# DAU_Kupplung_3phasig_V1_8.net
KiCad netlist of a schematic drawn in EAGLE
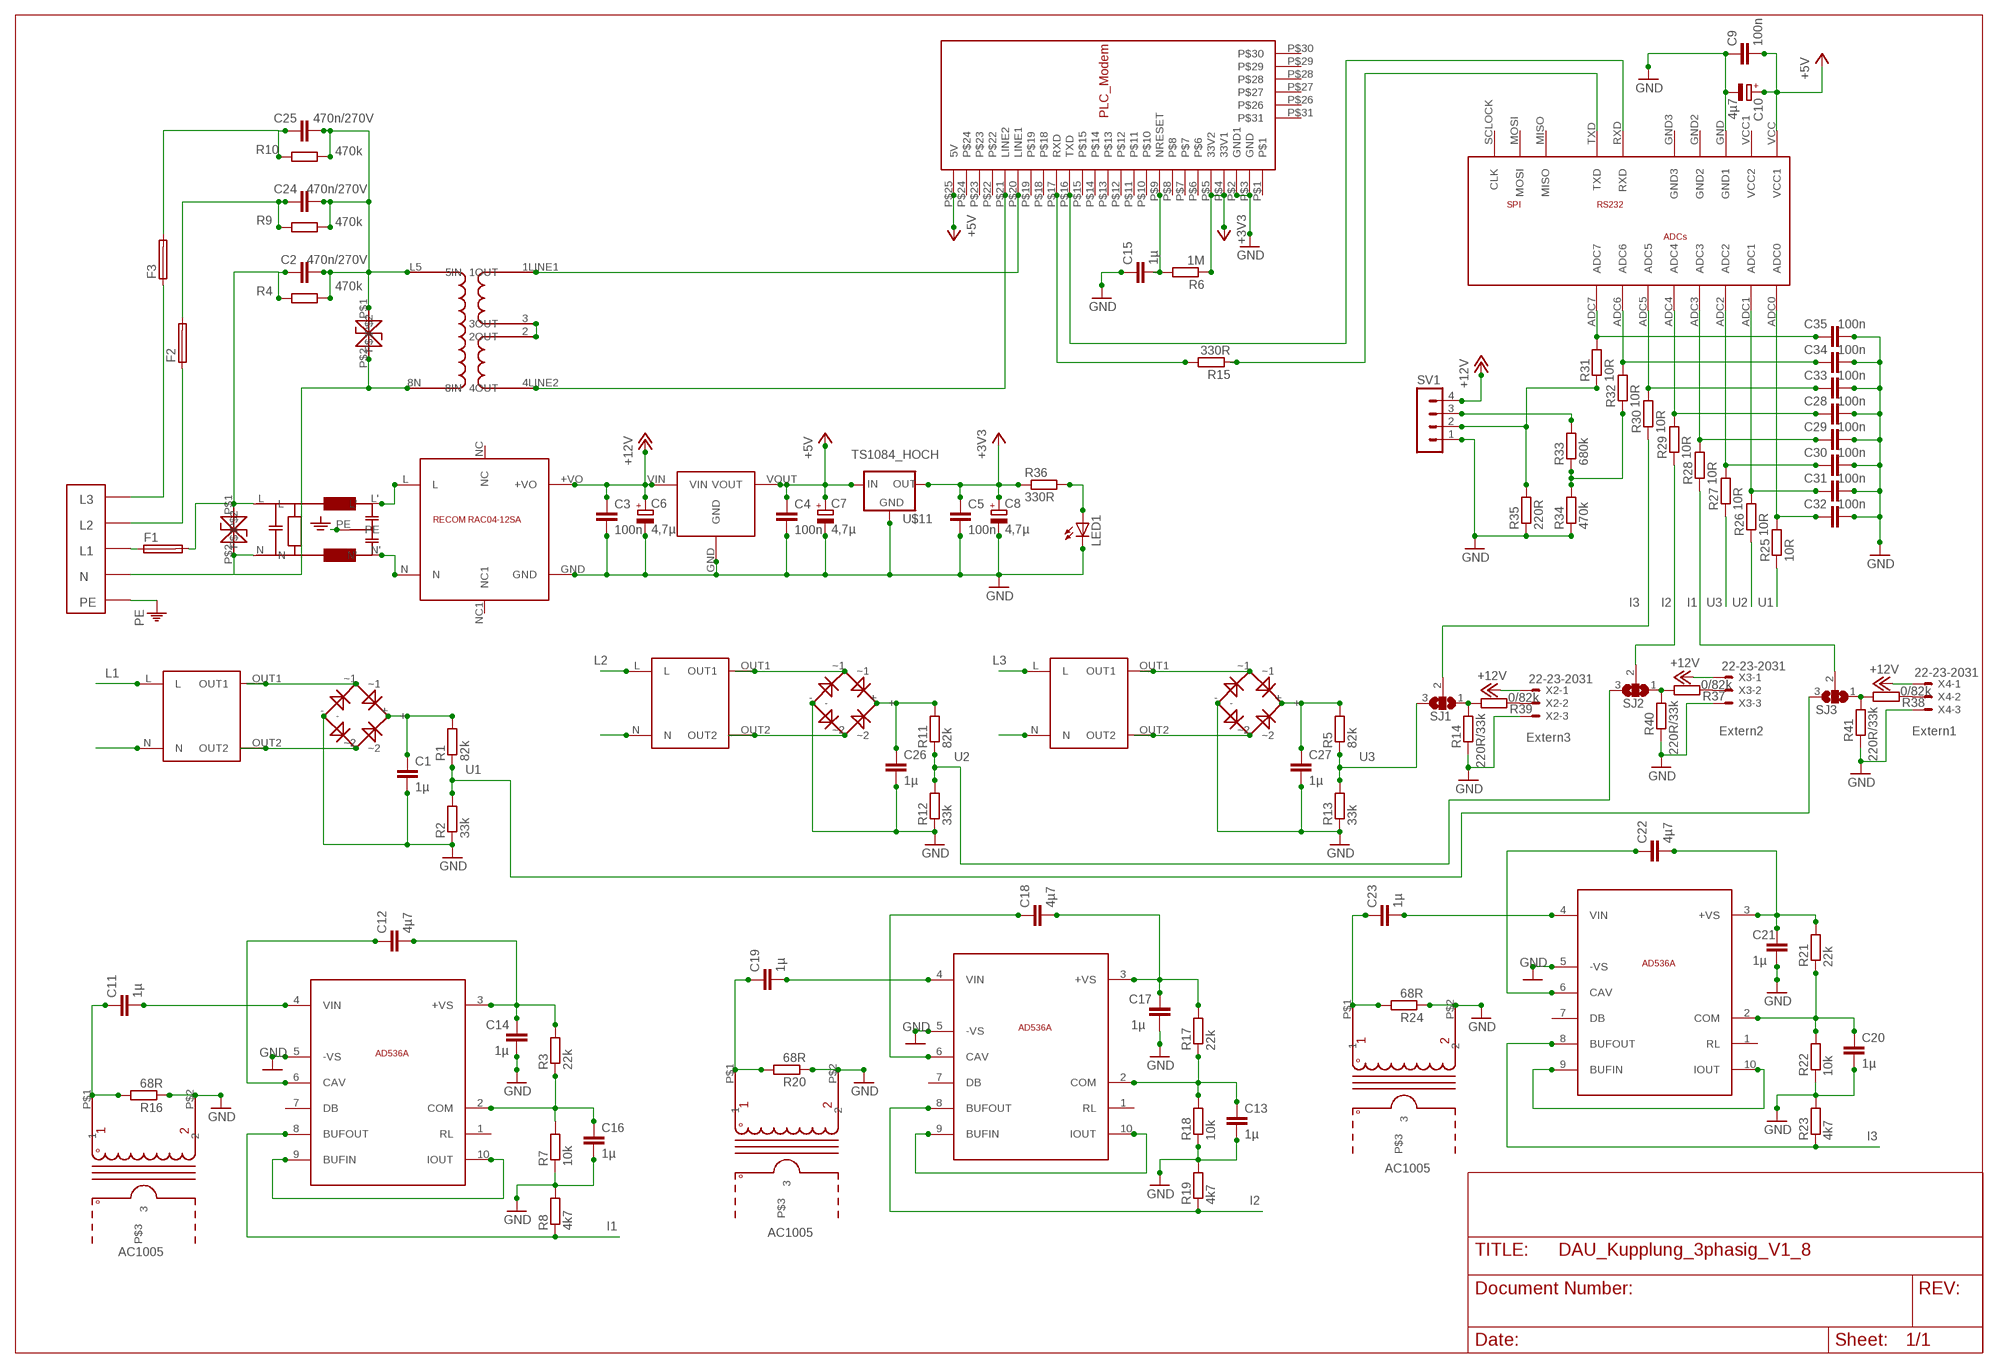
[diagram p0: schematic, sheet 1]

(export (version "E")
  (design (tool "Eeschema 10.0.6"))
  (components
    (comp (ref "AC1002_1")
      (value "AC1010")
      (footprint "eagle-import:AC1010")
      (libsource (lib "eagle-import") (part "AC1010"))
    )
    (comp (ref "C1")
      (value "1µ")
      (footprint "eagle-import:C0805K")
      (libsource (lib "eagle-import") (part "C-EUC0805K"))
    )
    (comp (ref "C2")
      (value "470n/270V")
      (footprint "eagle-import:C225-087X268")
      (libsource (lib "eagle-import") (part "C-EU225-087X268"))
    )
    (comp (ref "C3")
      (value "100n")
      (footprint "eagle-import:C0805K")
      (libsource (lib "eagle-import") (part "C-EUC0805K"))
    )
    (comp (ref "C4")
      (value "100n")
      (footprint "eagle-import:C0805K")
      (libsource (lib "eagle-import") (part "C-EUC0805K"))
    )
    (comp (ref "C5")
      (value "100n")
      (footprint "eagle-import:C0805K")
      (libsource (lib "eagle-import") (part "C-EUC0805K"))
    )
    (comp (ref "C6")
      (value "4,7µ")
      (footprint "eagle-import:E2,5-6")
      (libsource (lib "eagle-import") (part "resistor_CPOL-EUE2.5-6"))
    )
    (comp (ref "C7")
      (value "4,7µ")
      (footprint "eagle-import:E2,5-6")
      (libsource (lib "eagle-import") (part "resistor_CPOL-EUE2.5-6"))
    )
    (comp (ref "C8")
      (value "4,7µ")
      (footprint "eagle-import:E2,5-6")
      (libsource (lib "eagle-import") (part "resistor_CPOL-EUE2.5-6"))
    )
    (comp (ref "C9")
      (value "100n")
      (footprint "eagle-import:C0805K")
      (libsource (lib "eagle-import") (part "C-EUC0805K"))
    )
    (comp (ref "C10")
      (value "4µ7")
      (footprint "eagle-import:E2,5-6E")
      (libsource (lib "eagle-import") (part "CPOL-EUE2,5-6E"))
    )
    (comp (ref "C11")
      (value "1µ")
      (footprint "eagle-import:C0805K")
      (libsource (lib "eagle-import") (part "C-EUC0805K"))
    )
    (comp (ref "C12")
      (value "4µ7")
      (footprint "eagle-import:C0805K")
      (libsource (lib "eagle-import") (part "C-EUC0805K"))
    )
    (comp (ref "C13")
      (value "1µ")
      (footprint "eagle-import:C0805K")
      (libsource (lib "eagle-import") (part "C-EUC0805K"))
    )
    (comp (ref "C14")
      (value "1µ")
      (footprint "eagle-import:C0805K")
      (libsource (lib "eagle-import") (part "C-EUC0805K"))
    )
    (comp (ref "C15")
      (value "1µ")
      (footprint "eagle-import:C0805K")
      (libsource (lib "eagle-import") (part "C-EUC0805K"))
    )
    (comp (ref "C16")
      (value "1µ")
      (footprint "eagle-import:C0805K")
      (libsource (lib "eagle-import") (part "C-EUC0805K"))
    )
    (comp (ref "C17")
      (value "1µ")
      (footprint "eagle-import:C0805K")
      (libsource (lib "eagle-import") (part "C-EUC0805K"))
    )
    (comp (ref "C18")
      (value "4µ7")
      (footprint "eagle-import:C0805K")
      (libsource (lib "eagle-import") (part "C-EUC0805K"))
    )
    (comp (ref "C19")
      (value "1µ")
      (footprint "eagle-import:C0805K")
      (libsource (lib "eagle-import") (part "C-EUC0805K"))
    )
    (comp (ref "C20")
      (value "1µ")
      (footprint "eagle-import:C0805K")
      (libsource (lib "eagle-import") (part "C-EUC0805K"))
    )
    (comp (ref "C21")
      (value "1µ")
      (footprint "eagle-import:C0805K")
      (libsource (lib "eagle-import") (part "C-EUC0805K"))
    )
    (comp (ref "C22")
      (value "4µ7")
      (footprint "eagle-import:C0805K")
      (libsource (lib "eagle-import") (part "C-EUC0805K"))
    )
    (comp (ref "C23")
      (value "1µ")
      (footprint "eagle-import:C0805K")
      (libsource (lib "eagle-import") (part "C-EUC0805K"))
    )
    (comp (ref "C24")
      (value "470n/270V")
      (footprint "eagle-import:C225-087X268")
      (libsource (lib "eagle-import") (part "C-EU225-087X268"))
    )
    (comp (ref "C25")
      (value "470n/270V")
      (footprint "eagle-import:C225-087X268")
      (libsource (lib "eagle-import") (part "C-EU225-087X268"))
    )
    (comp (ref "C26")
      (value "1µ")
      (footprint "eagle-import:C0805K")
      (libsource (lib "eagle-import") (part "C-EUC0805K"))
    )
    (comp (ref "C27")
      (value "1µ")
      (footprint "eagle-import:C0805K")
      (libsource (lib "eagle-import") (part "C-EUC0805K"))
    )
    (comp (ref "C28")
      (value "100n")
      (footprint "eagle-import:C0805K")
      (libsource (lib "eagle-import") (part "C-EUC0805K"))
    )
    (comp (ref "C29")
      (value "100n")
      (footprint "eagle-import:C0805K")
      (libsource (lib "eagle-import") (part "C-EUC0805K"))
    )
    (comp (ref "C30")
      (value "100n")
      (footprint "eagle-import:C0805K")
      (libsource (lib "eagle-import") (part "C-EUC0805K"))
    )
    (comp (ref "C31")
      (value "100n")
      (footprint "eagle-import:C0805K")
      (libsource (lib "eagle-import") (part "C-EUC0805K"))
    )
    (comp (ref "C32")
      (value "100n")
      (footprint "eagle-import:C0805K")
      (libsource (lib "eagle-import") (part "C-EUC0805K"))
    )
    (comp (ref "C33")
      (value "100n")
      (footprint "eagle-import:C0805K")
      (libsource (lib "eagle-import") (part "C-EUC0805K"))
    )
    (comp (ref "C34")
      (value "100n")
      (footprint "eagle-import:C0805K")
      (libsource (lib "eagle-import") (part "C-EUC0805K"))
    )
    (comp (ref "C35")
      (value "100n")
      (footprint "eagle-import:C0805K")
      (libsource (lib "eagle-import") (part "C-EUC0805K"))
    )
    (comp (ref "F1")
      (value "TR5")
      (footprint "eagle-import:TR5")
      (libsource (lib "eagle-import") (part "TR5"))
    )
    (comp (ref "F2")
      (value "TR5")
      (footprint "eagle-import:TR5")
      (fields (field (name "OC_FARNELL") "unknown") (field (name "OC_NEWARK") "unknown"))
      (libsource (lib "eagle-import") (part "TR5"))
    )
    (comp (ref "F3")
      (value "TR5")
      (footprint "eagle-import:TR5")
      (fields (field (name "OC_FARNELL") "unknown") (field (name "OC_NEWARK") "unknown"))
      (libsource (lib "eagle-import") (part "TR5"))
    )
    (comp (ref "LED1")
      (value "LEDSQR2X5")
      (footprint "eagle-import:LED2X5")
      (libsource (lib "eagle-import") (part "LEDSQR2X5"))
    )
    (comp (ref "P6KE300CA")
      (value "P6KE300CA")
      (footprint "eagle-import:TSV")
      (libsource (lib "eagle-import") (part "TSV"))
    )
    (comp (ref "R1")
      (value "82k")
      (footprint "eagle-import:R0805")
      (libsource (lib "eagle-import") (part "R-EU_R0805"))
    )
    (comp (ref "R2")
      (value "33k")
      (footprint "eagle-import:R0805")
      (libsource (lib "eagle-import") (part "R-EU_R0805"))
    )
    (comp (ref "R3")
      (value "22k")
      (footprint "eagle-import:R0805")
      (libsource (lib "eagle-import") (part "R-EU_R0805"))
    )
    (comp (ref "R4")
      (value "470k")
      (footprint "eagle-import:0204_7")
      (libsource (lib "eagle-import") (part "R-EU_0204/7"))
    )
    (comp (ref "R5")
      (value "82k")
      (footprint "eagle-import:R0805")
      (libsource (lib "eagle-import") (part "R-EU_R0805"))
    )
    (comp (ref "R6")
      (value "1M")
      (footprint "eagle-import:R0805")
      (libsource (lib "eagle-import") (part "R-EU_R0805"))
    )
    (comp (ref "R7")
      (value "10k")
      (footprint "eagle-import:R0805")
      (libsource (lib "eagle-import") (part "R-EU_R0805"))
    )
    (comp (ref "R8")
      (value "4k7")
      (footprint "eagle-import:R0805")
      (libsource (lib "eagle-import") (part "R-EU_R0805"))
    )
    (comp (ref "R9")
      (value "470k")
      (footprint "eagle-import:0204_7")
      (libsource (lib "eagle-import") (part "R-EU_0204/7"))
    )
    (comp (ref "R10")
      (value "470k")
      (footprint "eagle-import:0204_7")
      (libsource (lib "eagle-import") (part "R-EU_0204/7"))
    )
    (comp (ref "R11")
      (value "82k")
      (footprint "eagle-import:R0805")
      (libsource (lib "eagle-import") (part "R-EU_R0805"))
    )
    (comp (ref "R12")
      (value "33k")
      (footprint "eagle-import:R0805")
      (libsource (lib "eagle-import") (part "R-EU_R0805"))
    )
    (comp (ref "R13")
      (value "33k")
      (footprint "eagle-import:R0805")
      (libsource (lib "eagle-import") (part "R-EU_R0805"))
    )
    (comp (ref "R14")
      (value "220R/33k")
      (footprint "eagle-import:R0805")
      (libsource (lib "eagle-import") (part "R-EU_R0805"))
    )
    (comp (ref "R15")
      (value "330R")
      (footprint "eagle-import:R0805")
      (libsource (lib "eagle-import") (part "R-EU_R0805"))
    )
    (comp (ref "R16")
      (value "68R")
      (footprint "eagle-import:0204_7")
      (libsource (lib "eagle-import") (part "R-EU_0204/7"))
    )
    (comp (ref "R17")
      (value "22k")
      (footprint "eagle-import:R0805")
      (libsource (lib "eagle-import") (part "R-EU_R0805"))
    )
    (comp (ref "R18")
      (value "10k")
      (footprint "eagle-import:R0805")
      (libsource (lib "eagle-import") (part "R-EU_R0805"))
    )
    (comp (ref "R19")
      (value "4k7")
      (footprint "eagle-import:R0805")
      (libsource (lib "eagle-import") (part "R-EU_R0805"))
    )
    (comp (ref "R20")
      (value "68R")
      (footprint "eagle-import:0204_7")
      (libsource (lib "eagle-import") (part "R-EU_0204/7"))
    )
    (comp (ref "R21")
      (value "22k")
      (footprint "eagle-import:R0805")
      (libsource (lib "eagle-import") (part "R-EU_R0805"))
    )
    (comp (ref "R22")
      (value "10k")
      (footprint "eagle-import:R0805")
      (libsource (lib "eagle-import") (part "R-EU_R0805"))
    )
    (comp (ref "R23")
      (value "4k7")
      (footprint "eagle-import:R0805")
      (libsource (lib "eagle-import") (part "R-EU_R0805"))
    )
    (comp (ref "R24")
      (value "68R")
      (footprint "eagle-import:0204_7")
      (libsource (lib "eagle-import") (part "R-EU_0204/7"))
    )
    (comp (ref "R25")
      (value "10R")
      (footprint "eagle-import:R0805")
      (libsource (lib "eagle-import") (part "R-EU_R0805"))
    )
    (comp (ref "R26")
      (value "10R")
      (footprint "eagle-import:R0805")
      (libsource (lib "eagle-import") (part "R-EU_R0805"))
    )
    (comp (ref "R27")
      (value "10R")
      (footprint "eagle-import:R0805")
      (libsource (lib "eagle-import") (part "R-EU_R0805"))
    )
    (comp (ref "R28")
      (value "10R")
      (footprint "eagle-import:R0805")
      (libsource (lib "eagle-import") (part "R-EU_R0805"))
    )
    (comp (ref "R29")
      (value "10R")
      (footprint "eagle-import:R0805")
      (libsource (lib "eagle-import") (part "R-EU_R0805"))
    )
    (comp (ref "R30")
      (value "10R")
      (footprint "eagle-import:R0805")
      (libsource (lib "eagle-import") (part "R-EU_R0805"))
    )
    (comp (ref "R31")
      (value "10R")
      (footprint "eagle-import:R0805")
      (libsource (lib "eagle-import") (part "R-EU_R0805"))
    )
    (comp (ref "R32")
      (value "10R")
      (footprint "eagle-import:R0805")
      (libsource (lib "eagle-import") (part "R-EU_R0805"))
    )
    (comp (ref "R33")
      (value "680k")
      (footprint "eagle-import:R0805")
      (libsource (lib "eagle-import") (part "R-EU_R0805"))
    )
    (comp (ref "R34")
      (value "470k")
      (footprint "eagle-import:R0805")
      (libsource (lib "eagle-import") (part "R-EU_R0805"))
    )
    (comp (ref "R35")
      (value "220R")
      (footprint "eagle-import:R0805")
      (libsource (lib "eagle-import") (part "R-EU_R0805"))
    )
    (comp (ref "R36")
      (value "330R")
      (footprint "eagle-import:R0805")
      (libsource (lib "eagle-import") (part "R-EU_R0805"))
    )
    (comp (ref "R37")
      (value "0/82k")
      (footprint "eagle-import:R0805")
      (libsource (lib "eagle-import") (part "R-EU_R0805"))
    )
    (comp (ref "R38")
      (value "0/82k")
      (footprint "eagle-import:R0805")
      (libsource (lib "eagle-import") (part "R-EU_R0805"))
    )
    (comp (ref "R39")
      (value "0/82k")
      (footprint "eagle-import:R0805")
      (libsource (lib "eagle-import") (part "R-EU_R0805"))
    )
    (comp (ref "R40")
      (value "220R/33k")
      (footprint "eagle-import:R0805")
      (libsource (lib "eagle-import") (part "R-EU_R0805"))
    )
    (comp (ref "R41")
      (value "220R/33k")
      (footprint "eagle-import:R0805")
      (libsource (lib "eagle-import") (part "R-EU_R0805"))
    )
    (comp (ref "SJ1")
      (value "SJ2WW")
      (footprint "eagle-import:SJ_2W")
      (libsource (lib "eagle-import") (part "SJ2WW"))
    )
    (comp (ref "SJ2")
      (value "SJ2WW")
      (footprint "eagle-import:SJ_2W")
      (libsource (lib "eagle-import") (part "SJ2WW"))
    )
    (comp (ref "SJ3")
      (value "SJ2WW")
      (footprint "eagle-import:SJ_2W")
      (libsource (lib "eagle-import") (part "SJ2WW"))
    )
    (comp (ref "SV1")
      (value "MA04-1")
      (footprint "eagle-import:MA04-1")
      (libsource (lib "eagle-import") (part "MA04-1"))
    )
    (comp (ref "TSV2")
      (value "TSV")
      (footprint "eagle-import:TSV")
      (libsource (lib "eagle-import") (part "TSV"))
    )
    (comp (ref "U$1")
      (value "RECOM_RAC04_12SA")
      (footprint "eagle-import:RAC04_12SA")
      (libsource (lib "eagle-import") (part "RECOM_RAC04_12SA"))
    )
    (comp (ref "U$2")
      (value "SICHERHEITSTRAFO")
      (footprint "eagle-import:TRAFO_0,35VA")
      (libsource (lib "eagle-import") (part "SICHERHEITSTRAFO"))
    )
    (comp (ref "U$3")
      (value "ADUC831_MINIMUM")
      (footprint "eagle-import:ADUC_MINIMUM")
      (libsource (lib "eagle-import") (part "ADUC831_MINIMUM"))
    )
    (comp (ref "U$4")
      (value "MODEMSTECKER")
      (footprint "eagle-import:MODEM_FUSS")
      (libsource (lib "eagle-import") (part "MODEMSTECKER"))
    )
    (comp (ref "U$5")
      (value "PLC_UEBERTRAGER_V2")
      (footprint "eagle-import:PLC-UEBERTRAGER_V2")
      (libsource (lib "eagle-import") (part "PLC_UEBERTRAGER_V2"))
    )
    (comp (ref "U$7")
      (value "AC1010")
      (footprint "eagle-import:AC1010")
      (libsource (lib "eagle-import") (part "AC1010"))
    )
    (comp (ref "U$8")
      (value "RECTIFIER")
      (footprint "eagle-import:RECTIFIER")
      (libsource (lib "eagle-import") (part "RECTIFIER"))
    )
    (comp (ref "U$10")
      (value "RECOM_785_05")
      (footprint "eagle-import:RECOM785X")
      (libsource (lib "eagle-import") (part "RECOM_785_05"))
    )
    (comp (ref "U$11")
      (value "TS1084_HOCH")
      (footprint "eagle-import:TS1084_HOCH")
      (libsource (lib "eagle-import") (part "TS1084_HOCH"))
    )
    (comp (ref "U$12")
      (value "AD536")
      (footprint "eagle-import:TO100_10PIN")
      (libsource (lib "eagle-import") (part "AD536"))
    )
    (comp (ref "U$13")
      (value "AD536")
      (footprint "eagle-import:TO100_10PIN")
      (libsource (lib "eagle-import") (part "AD536"))
    )
    (comp (ref "U$14")
      (value "AC1010")
      (footprint "eagle-import:AC1010")
      (libsource (lib "eagle-import") (part "AC1010"))
    )
    (comp (ref "U$15")
      (value "AD536")
      (footprint "eagle-import:TO100_10PIN")
      (libsource (lib "eagle-import") (part "AD536"))
    )
    (comp (ref "U$16")
      (value "SICHERHEITSTRAFO")
      (footprint "eagle-import:TRAFO_0,35VA")
      (libsource (lib "eagle-import") (part "SICHERHEITSTRAFO"))
    )
    (comp (ref "U$17")
      (value "RECTIFIER")
      (footprint "eagle-import:RECTIFIER")
      (libsource (lib "eagle-import") (part "RECTIFIER"))
    )
    (comp (ref "U$18")
      (value "SICHERHEITSTRAFO")
      (footprint "eagle-import:TRAFO_0,35VA")
      (libsource (lib "eagle-import") (part "SICHERHEITSTRAFO"))
    )
    (comp (ref "U$19")
      (value "RECTIFIER")
      (footprint "eagle-import:RECTIFIER")
      (libsource (lib "eagle-import") (part "RECTIFIER"))
    )
    (comp (ref "U$20")
      (value "NETZFILTER_05_A")
      (footprint "eagle-import:NETZFILTER")
      (libsource (lib "eagle-import") (part "NETZFILTER_05_A"))
    )
    (comp (ref "X1")
      (value "CONNECTO_5_POL")
      (footprint "eagle-import:CONNECTOR_5_POL")
      (libsource (lib "eagle-import") (part "CONNECTO_5_POL"))
    )
    (comp (ref "X2")
      (value "22-23-2031")
      (footprint "eagle-import:22-23-2031")
      (fields (field (name "MF") "MOLEX"))
      (libsource (lib "eagle-import") (part "22-23-2031"))
    )
    (comp (ref "X3")
      (value "22-23-2031")
      (footprint "eagle-import:22-23-2031")
      (fields (field (name "MF") "MOLEX"))
      (libsource (lib "eagle-import") (part "22-23-2031"))
    )
    (comp (ref "X4")
      (value "22-23-2031")
      (footprint "eagle-import:22-23-2031")
      (fields (field (name "MF") "MOLEX"))
      (libsource (lib "eagle-import") (part "22-23-2031"))
    )
  )
  (nets
    (net (code "1") (name "+3V3") (class "Default")
      (node (ref "C5") (pin "1") (pinfunction "1_1") (pintype "passive"))
      (node (ref "C8") (pin "+") (pinfunction "+_+") (pintype "passive"))
      (node (ref "R36") (pin "1") (pinfunction "1_1") (pintype "passive"))
      (node (ref "R6") (pin "1") (pinfunction "1_1") (pintype "passive"))
      (node (ref "U$11") (pin "OUT") (pinfunction "OUT_OUT") (pintype "passive"))
      (node (ref "U$4") (pin "P$4") (pinfunction "33V1_P$4") (pintype "bidirectional"))
      (node (ref "U$4") (pin "P$5") (pinfunction "33V2_P$5") (pintype "bidirectional"))
    )
    (net (code "2") (name "+5V") (class "Default")
      (node (ref "C10") (pin "+") (pinfunction "+_+") (pintype "passive"))
      (node (ref "C4") (pin "1") (pinfunction "1_1") (pintype "passive"))
      (node (ref "C7") (pin "+") (pinfunction "+_+") (pintype "passive"))
      (node (ref "C9") (pin "2") (pinfunction "2_2") (pintype "passive"))
      (node (ref "U$10") (pin "VOUT") (pinfunction "VOUT_VOUT") (pintype "bidirectional"))
      (node (ref "U$11") (pin "IN") (pinfunction "IN_IN") (pintype "input"))
      (node (ref "U$3") (pin "VCC") (pinfunction "VCC1_VCC") (pintype "bidirectional"))
      (node (ref "U$4") (pin "P$25") (pinfunction "5V_P$25") (pintype "bidirectional"))
    )
    (net (code "3") (name "+12V") (class "Default")
      (node (ref "C3") (pin "1") (pinfunction "1_1") (pintype "passive"))
      (node (ref "C6") (pin "+") (pinfunction "+_+") (pintype "passive"))
      (node (ref "SV1") (pin "4") (pinfunction "4_4") (pintype "passive"))
      (node (ref "U$1") (pin "+VO") (pinfunction "+VO_+VO") (pintype "bidirectional"))
      (node (ref "U$10") (pin "VIN") (pinfunction "VIN_VIN") (pintype "bidirectional"))
      (node (ref "X2") (pin "1") (pinfunction "S_1") (pintype "passive"))
      (node (ref "X3") (pin "1") (pinfunction "S_1") (pintype "passive"))
      (node (ref "X4") (pin "1") (pinfunction "S_1") (pintype "passive"))
    )
    (net (code "4") (name "/I1") (class "Default")
      (node (ref "R28") (pin "1") (pinfunction "1_1") (pintype "passive"))
      (node (ref "R8") (pin "1") (pinfunction "1_1") (pintype "passive"))
      (node (ref "SJ3") (pin "2") (pinfunction "2_2") (pintype "passive"))
      (node (ref "U$13") (pin "8") (pinfunction "BUFOUT_8") (pintype "bidirectional"))
    )
    (net (code "5") (name "/I2") (class "Default")
      (node (ref "R19") (pin "1") (pinfunction "1_1") (pintype "passive"))
      (node (ref "R29") (pin "1") (pinfunction "1_1") (pintype "passive"))
      (node (ref "SJ2") (pin "2") (pinfunction "2_2") (pintype "passive"))
      (node (ref "U$12") (pin "8") (pinfunction "BUFOUT_8") (pintype "bidirectional"))
    )
    (net (code "6") (name "/I3") (class "Default")
      (node (ref "R23") (pin "1") (pinfunction "1_1") (pintype "passive"))
      (node (ref "R30") (pin "1") (pinfunction "1_1") (pintype "passive"))
      (node (ref "SJ1") (pin "2") (pinfunction "2_2") (pintype "passive"))
      (node (ref "U$15") (pin "8") (pinfunction "BUFOUT_8") (pintype "bidirectional"))
    )
    (net (code "7") (name "/L1") (class "Default")
      (node (ref "C2") (pin "1") (pinfunction "1_1") (pintype "passive"))
      (node (ref "F1") (pin "2") (pinfunction "2_2") (pintype "passive"))
      (node (ref "P6KE300CA") (pin "P$1") (pinfunction "P$1_P$1") (pintype "bidirectional"))
      (node (ref "R4") (pin "2") (pinfunction "2_2") (pintype "passive"))
      (node (ref "U$2") (pin "L") (pinfunction "L_L") (pintype "bidirectional"))
      (node (ref "U$20") (pin "L") (pinfunction "L_L") (pintype "bidirectional"))
    )
    (net (code "8") (name "/L2") (class "Default")
      (node (ref "C24") (pin "1") (pinfunction "1_1") (pintype "passive"))
      (node (ref "F2") (pin "2") (pinfunction "2_2") (pintype "passive"))
      (node (ref "R9") (pin "2") (pinfunction "2_2") (pintype "passive"))
      (node (ref "U$16") (pin "L") (pinfunction "L_L") (pintype "bidirectional"))
    )
    (net (code "9") (name "/L3") (class "Default")
      (node (ref "C25") (pin "1") (pinfunction "1_1") (pintype "passive"))
      (node (ref "F3") (pin "2") (pinfunction "2_2") (pintype "passive"))
      (node (ref "R10") (pin "2") (pinfunction "2_2") (pintype "passive"))
      (node (ref "U$18") (pin "L") (pinfunction "L_L") (pintype "bidirectional"))
    )
    (net (code "10") (name "/N") (class "Default")
      (node (ref "P6KE300CA") (pin "P$2") (pinfunction "P$2_P$2") (pintype "bidirectional"))
      (node (ref "TSV2") (pin "P$2") (pinfunction "P$2_P$2") (pintype "bidirectional"))
      (node (ref "U$16") (pin "N") (pinfunction "N_N") (pintype "bidirectional"))
      (node (ref "U$18") (pin "N") (pinfunction "N_N") (pintype "bidirectional"))
      (node (ref "U$2") (pin "N") (pinfunction "N_N") (pintype "bidirectional"))
      (node (ref "U$20") (pin "N") (pinfunction "N_N") (pintype "bidirectional"))
      (node (ref "U$5") (pin "8N") (pinfunction "8IN_8N") (pintype "input"))
      (node (ref "X1") (pin "P$4") (pinfunction "P$4_P$4") (pintype "bidirectional"))
    )
    (net (code "11") (name "/U1") (class "Default")
      (node (ref "R1") (pin "1") (pinfunction "1_1") (pintype "passive"))
      (node (ref "R2") (pin "2") (pinfunction "2_2") (pintype "passive"))
      (node (ref "R25") (pin "1") (pinfunction "1_1") (pintype "passive"))
      (node (ref "SJ3") (pin "3") (pinfunction "3_3") (pintype "passive"))
    )
    (net (code "12") (name "/U2") (class "Default")
      (node (ref "R11") (pin "1") (pinfunction "1_1") (pintype "passive"))
      (node (ref "R12") (pin "2") (pinfunction "2_2") (pintype "passive"))
      (node (ref "R26") (pin "1") (pinfunction "1_1") (pintype "passive"))
      (node (ref "SJ2") (pin "3") (pinfunction "3_3") (pintype "passive"))
    )
    (net (code "13") (name "/U3") (class "Default")
      (node (ref "R13") (pin "2") (pinfunction "2_2") (pintype "passive"))
      (node (ref "R27") (pin "1") (pinfunction "1_1") (pintype "passive"))
      (node (ref "R5") (pin "1") (pinfunction "1_1") (pintype "passive"))
      (node (ref "SJ1") (pin "3") (pinfunction "3_3") (pintype "passive"))
    )
    (net (code "14") (name "GND") (class "Default")
      (node (ref "AC1002_1") (pin "P$2") (pinfunction "2_P$2") (pintype "output"))
      (node (ref "C1") (pin "2") (pinfunction "2_2") (pintype "passive"))
      (node (ref "C10") (pin "-") (pinfunction "-_-") (pintype "passive"))
      (node (ref "C13") (pin "2") (pinfunction "2_2") (pintype "passive"))
      (node (ref "C14") (pin "1") (pinfunction "1_1") (pintype "passive"))
      (node (ref "C15") (pin "1") (pinfunction "1_1") (pintype "passive"))
      (node (ref "C16") (pin "2") (pinfunction "2_2") (pintype "passive"))
      (node (ref "C17") (pin "1") (pinfunction "1_1") (pintype "passive"))
      (node (ref "C20") (pin "2") (pinfunction "2_2") (pintype "passive"))
      (node (ref "C21") (pin "2") (pinfunction "2_2") (pintype "passive"))
      (node (ref "C26") (pin "2") (pinfunction "2_2") (pintype "passive"))
      (node (ref "C27") (pin "2") (pinfunction "2_2") (pintype "passive"))
      (node (ref "C28") (pin "2") (pinfunction "2_2") (pintype "passive"))
      (node (ref "C29") (pin "2") (pinfunction "2_2") (pintype "passive"))
      (node (ref "C3") (pin "2") (pinfunction "2_2") (pintype "passive"))
      (node (ref "C30") (pin "2") (pinfunction "2_2") (pintype "passive"))
      (node (ref "C31") (pin "2") (pinfunction "2_2") (pintype "passive"))
      (node (ref "C32") (pin "2") (pinfunction "2_2") (pintype "passive"))
      (node (ref "C33") (pin "2") (pinfunction "2_2") (pintype "passive"))
      (node (ref "C34") (pin "2") (pinfunction "2_2") (pintype "passive"))
      (node (ref "C35") (pin "2") (pinfunction "2_2") (pintype "passive"))
      (node (ref "C4") (pin "2") (pinfunction "2_2") (pintype "passive"))
      (node (ref "C5") (pin "2") (pinfunction "2_2") (pintype "passive"))
      (node (ref "C6") (pin "-") (pinfunction "-_-") (pintype "passive"))
      (node (ref "C7") (pin "-") (pinfunction "-_-") (pintype "passive"))
      (node (ref "C8") (pin "-") (pinfunction "-_-") (pintype "passive"))
      (node (ref "C9") (pin "1") (pinfunction "1_1") (pintype "passive"))
      (node (ref "LED1") (pin "K") (pinfunction "C_K") (pintype "passive"))
      (node (ref "R12") (pin "1") (pinfunction "1_1") (pintype "passive"))
      (node (ref "R13") (pin "1") (pinfunction "1_1") (pintype "passive"))
      (node (ref "R14") (pin "1") (pinfunction "1_1") (pintype "passive"))
      (node (ref "R16") (pin "1") (pinfunction "1_1") (pintype "passive"))
      (node (ref "R18") (pin "1") (pinfunction "1_1") (pintype "passive"))
      (node (ref "R19") (pin "2") (pinfunction "2_2") (pintype "passive"))
      (node (ref "R2") (pin "1") (pinfunction "1_1") (pintype "passive"))
      (node (ref "R20") (pin "1") (pinfunction "1_1") (pintype "passive"))
      (node (ref "R22") (pin "1") (pinfunction "1_1") (pintype "passive"))
      (node (ref "R23") (pin "2") (pinfunction "2_2") (pintype "passive"))
      (node (ref "R24") (pin "1") (pinfunction "1_1") (pintype "passive"))
      (node (ref "R34") (pin "1") (pinfunction "1_1") (pintype "passive"))
      (node (ref "R35") (pin "1") (pinfunction "1_1") (pintype "passive"))
      (node (ref "R40") (pin "1") (pinfunction "1_1") (pintype "passive"))
      (node (ref "R41") (pin "1") (pinfunction "1_1") (pintype "passive"))
      (node (ref "R7") (pin "1") (pinfunction "1_1") (pintype "passive"))
      (node (ref "R8") (pin "2") (pinfunction "2_2") (pintype "passive"))
      (node (ref "SV1") (pin "1") (pinfunction "1_1") (pintype "passive"))
      (node (ref "U$1") (pin "GND") (pinfunction "GND_GND") (pintype "bidirectional"))
      (node (ref "U$10") (pin "GND") (pinfunction "GND_GND") (pintype "bidirectional"))
      (node (ref "U$11") (pin "GND") (pinfunction "GND_GND") (pintype "input"))
      (node (ref "U$12") (pin "5") (pinfunction "-VS_5") (pintype "bidirectional"))
      (node (ref "U$13") (pin "5") (pinfunction "-VS_5") (pintype "bidirectional"))
      (node (ref "U$14") (pin "P$2") (pinfunction "2_P$2") (pintype "output"))
      (node (ref "U$15") (pin "5") (pinfunction "-VS_5") (pintype "bidirectional"))
      (node (ref "U$17") (pin "-") (pinfunction "-_-") (pintype "bidirectional"))
      (node (ref "U$19") (pin "-") (pinfunction "-_-") (pintype "bidirectional"))
      (node (ref "U$3") (pin "GND") (pinfunction "GND1_GND") (pintype "bidirectional"))
      (node (ref "U$4") (pin "P$2") (pinfunction "GND1_P$2") (pintype "bidirectional"))
      (node (ref "U$4") (pin "P$3") (pinfunction "GND_P$3") (pintype "bidirectional"))
      (node (ref "U$7") (pin "P$2") (pinfunction "2_P$2") (pintype "output"))
      (node (ref "U$8") (pin "-") (pinfunction "-_-") (pintype "bidirectional"))
      (node (ref "X2") (pin "3") (pinfunction "S_3") (pintype "passive"))
      (node (ref "X3") (pin "3") (pinfunction "S_3") (pintype "passive"))
      (node (ref "X4") (pin "3") (pinfunction "S_3") (pintype "passive"))
    )
    (net (code "15") (name "Net-(AC1002_1-1)") (class "Default")
      (node (ref "AC1002_1") (pin "P$1") (pinfunction "1_P$1") (pintype "output"))
      (node (ref "C11") (pin "1") (pinfunction "1_1") (pintype "passive"))
      (node (ref "R16") (pin "2") (pinfunction "2_2") (pintype "passive"))
    )
    (net (code "16") (name "Net-(C1-Pad1)") (class "Default")
      (node (ref "C1") (pin "1") (pinfunction "1_1") (pintype "passive"))
      (node (ref "R1") (pin "2") (pinfunction "2_2") (pintype "passive"))
      (node (ref "U$8") (pin "+") (pinfunction "+_+") (pintype "bidirectional"))
    )
    (net (code "17") (name "Net-(C26-Pad1)") (class "Default")
      (node (ref "C26") (pin "1") (pinfunction "1_1") (pintype "passive"))
      (node (ref "R11") (pin "2") (pinfunction "2_2") (pintype "passive"))
      (node (ref "U$17") (pin "+") (pinfunction "+_+") (pintype "bidirectional"))
    )
    (net (code "18") (name "Net-(C27-Pad1)") (class "Default")
      (node (ref "C27") (pin "1") (pinfunction "1_1") (pintype "passive"))
      (node (ref "R5") (pin "2") (pinfunction "2_2") (pintype "passive"))
      (node (ref "U$19") (pin "+") (pinfunction "+_+") (pintype "bidirectional"))
    )
    (net (code "19") (name "Net-(C28-Pad1)") (class "Default")
      (node (ref "C28") (pin "1") (pinfunction "1_1") (pintype "passive"))
      (node (ref "R29") (pin "2") (pinfunction "2_2") (pintype "passive"))
      (node (ref "U$3") (pin "ADC4") (pinfunction "ADC4_ADC4") (pintype "bidirectional"))
    )
    (net (code "20") (name "Net-(C29-Pad1)") (class "Default")
      (node (ref "C29") (pin "1") (pinfunction "1_1") (pintype "passive"))
      (node (ref "R28") (pin "2") (pinfunction "2_2") (pintype "passive"))
      (node (ref "U$3") (pin "ADC3") (pinfunction "ADC3_ADC3") (pintype "bidirectional"))
    )
    (net (code "21") (name "Net-(C30-Pad1)") (class "Default")
      (node (ref "C30") (pin "1") (pinfunction "1_1") (pintype "passive"))
      (node (ref "R27") (pin "2") (pinfunction "2_2") (pintype "passive"))
      (node (ref "U$3") (pin "ADC2") (pinfunction "ADC2_ADC2") (pintype "bidirectional"))
    )
    (net (code "22") (name "Net-(C31-Pad1)") (class "Default")
      (node (ref "C31") (pin "1") (pinfunction "1_1") (pintype "passive"))
      (node (ref "R26") (pin "2") (pinfunction "2_2") (pintype "passive"))
      (node (ref "U$3") (pin "ADC1") (pinfunction "ADC1_ADC1") (pintype "bidirectional"))
    )
    (net (code "23") (name "Net-(C32-Pad1)") (class "Default")
      (node (ref "C32") (pin "1") (pinfunction "1_1") (pintype "passive"))
      (node (ref "R25") (pin "2") (pinfunction "2_2") (pintype "passive"))
      (node (ref "U$3") (pin "ADC0") (pinfunction "ADC0_ADC0") (pintype "bidirectional"))
    )
    (net (code "24") (name "Net-(C33-Pad1)") (class "Default")
      (node (ref "C33") (pin "1") (pinfunction "1_1") (pintype "passive"))
      (node (ref "R30") (pin "2") (pinfunction "2_2") (pintype "passive"))
      (node (ref "U$3") (pin "ADC5") (pinfunction "ADC5_ADC5") (pintype "bidirectional"))
    )
    (net (code "25") (name "Net-(C34-Pad1)") (class "Default")
      (node (ref "C34") (pin "1") (pinfunction "1_1") (pintype "passive"))
      (node (ref "R32") (pin "2") (pinfunction "2_2") (pintype "passive"))
      (node (ref "U$3") (pin "ADC6") (pinfunction "ADC6_ADC6") (pintype "bidirectional"))
    )
    (net (code "26") (name "Net-(C35-Pad1)") (class "Default")
      (node (ref "C35") (pin "1") (pinfunction "1_1") (pintype "passive"))
      (node (ref "R31") (pin "2") (pinfunction "2_2") (pintype "passive"))
      (node (ref "U$3") (pin "ADC7") (pinfunction "ADC7_ADC7") (pintype "bidirectional"))
    )
    (net (code "27") (name "Net-(F1-Pad1)") (class "Default")
      (node (ref "F1") (pin "1") (pinfunction "1_1") (pintype "passive"))
      (node (ref "X1") (pin "P$3") (pinfunction "P$3_P$3") (pintype "bidirectional"))
    )
    (net (code "28") (name "Net-(F2-Pad1)") (class "Default")
      (node (ref "F2") (pin "1") (pinfunction "1_1") (pintype "passive"))
      (node (ref "X1") (pin "P$2") (pinfunction "P$2_P$2") (pintype "bidirectional"))
    )
    (net (code "29") (name "Net-(F3-Pad1)") (class "Default")
      (node (ref "F3") (pin "1") (pinfunction "1_1") (pintype "passive"))
      (node (ref "X1") (pin "P$1") (pinfunction "P$1_P$1") (pintype "bidirectional"))
    )
    (net (code "30") (name "Net-(LED1-PadA)") (class "Default")
      (node (ref "LED1") (pin "A") (pinfunction "A_A") (pintype "passive"))
      (node (ref "R36") (pin "2") (pinfunction "2_2") (pintype "passive"))
    )
    (net (code "31") (name "Net-(R14-Pad2)") (class "Default")
      (node (ref "R14") (pin "2") (pinfunction "2_2") (pintype "passive"))
      (node (ref "R39") (pin "2") (pinfunction "2_2") (pintype "passive"))
      (node (ref "SJ1") (pin "1") (pinfunction "1_1") (pintype "passive"))
    )
    (net (code "32") (name "Net-(R15-Pad1)") (class "Default")
      (node (ref "R15") (pin "1") (pinfunction "1_1") (pintype "passive"))
      (node (ref "U$3") (pin "TXD") (pinfunction "TXD_TXD") (pintype "bidirectional"))
    )
    (net (code "33") (name "Net-(R31-Pad1)") (class "Default")
      (node (ref "R31") (pin "1") (pinfunction "1_1") (pintype "passive"))
      (node (ref "R35") (pin "2") (pinfunction "2_2") (pintype "passive"))
      (node (ref "SV1") (pin "2") (pinfunction "2_2") (pintype "passive"))
    )
    (net (code "34") (name "Net-(R32-Pad1)") (class "Default")
      (node (ref "R32") (pin "1") (pinfunction "1_1") (pintype "passive"))
      (node (ref "R33") (pin "1") (pinfunction "1_1") (pintype "passive"))
      (node (ref "R34") (pin "2") (pinfunction "2_2") (pintype "passive"))
    )
    (net (code "35") (name "Net-(R33-Pad2)") (class "Default")
      (node (ref "R33") (pin "2") (pinfunction "2_2") (pintype "passive"))
      (node (ref "SV1") (pin "3") (pinfunction "3_3") (pintype "passive"))
    )
    (net (code "36") (name "Net-(R37-Pad2)") (class "Default")
      (node (ref "R37") (pin "2") (pinfunction "2_2") (pintype "passive"))
      (node (ref "R40") (pin "2") (pinfunction "2_2") (pintype "passive"))
      (node (ref "SJ2") (pin "1") (pinfunction "1_1") (pintype "passive"))
    )
    (net (code "37") (name "Net-(R38-Pad2)") (class "Default")
      (node (ref "R38") (pin "2") (pinfunction "2_2") (pintype "passive"))
      (node (ref "R41") (pin "2") (pinfunction "2_2") (pintype "passive"))
      (node (ref "SJ3") (pin "1") (pinfunction "1_1") (pintype "passive"))
    )
    (net (code "38") (name "Net-(U$1-PadL)") (class "Default")
      (node (ref "U$1") (pin "L") (pinfunction "L_L") (pintype "bidirectional"))
      (node (ref "U$20") (pin "L'") (pinfunction "L'_L'") (pintype "bidirectional"))
    )
    (net (code "39") (name "Net-(U$1-PadN)") (class "Default")
      (node (ref "U$1") (pin "N") (pinfunction "N_N") (pintype "bidirectional"))
      (node (ref "U$20") (pin "N'") (pinfunction "N'_N'") (pintype "bidirectional"))
    )
    (net (code "40") (name "Net-(U$4-LINE1)") (class "Default")
      (node (ref "U$4") (pin "P$20") (pinfunction "LINE1_P$20") (pintype "bidirectional"))
      (node (ref "U$5") (pin "1LINE1") (pinfunction "1OUT_1LINE1") (pintype "output"))
    )
    (net (code "41") (name "Net-(U$4-LINE2)") (class "Default")
      (node (ref "U$4") (pin "P$21") (pinfunction "LINE2_P$21") (pintype "bidirectional"))
      (node (ref "U$5") (pin "4LINE2") (pinfunction "4OUT_4LINE2") (pintype "output"))
    )
    (net (code "42") (name "Net-(U$4-NRESET)") (class "Default")
      (node (ref "C15") (pin "2") (pinfunction "2_2") (pintype "passive"))
      (node (ref "R6") (pin "2") (pinfunction "2_2") (pintype "passive"))
      (node (ref "U$4") (pin "P$9") (pinfunction "NRESET_P$9") (pintype "bidirectional"))
    )
    (net (code "43") (name "Net-(U$4-RXD)") (class "Default")
      (node (ref "R15") (pin "2") (pinfunction "2_2") (pintype "passive"))
      (node (ref "U$4") (pin "P$17") (pinfunction "RXD_P$17") (pintype "bidirectional"))
    )
    (net (code "44") (name "Net-(U$4-TXD)") (class "Default")
      (node (ref "U$3") (pin "RXD") (pinfunction "RXD_RXD") (pintype "bidirectional"))
      (node (ref "U$4") (pin "P$16") (pinfunction "TXD_P$16") (pintype "bidirectional"))
    )
    (net (code "45") (name "Net-(U$5-2OUT)") (class "Default")
      (node (ref "U$5") (pin "2") (pinfunction "2OUT_2") (pintype "output"))
      (node (ref "U$5") (pin "3") (pinfunction "3OUT_3") (pintype "output"))
    )
    (net (code "46") (name "Net-(U$5-5IN)") (class "Default")
      (node (ref "C2") (pin "2") (pinfunction "2_2") (pintype "passive"))
      (node (ref "C24") (pin "2") (pinfunction "2_2") (pintype "passive"))
      (node (ref "C25") (pin "2") (pinfunction "2_2") (pintype "passive"))
      (node (ref "R10") (pin "1") (pinfunction "1_1") (pintype "passive"))
      (node (ref "R4") (pin "1") (pinfunction "1_1") (pintype "passive"))
      (node (ref "R9") (pin "1") (pinfunction "1_1") (pintype "passive"))
      (node (ref "TSV2") (pin "P$1") (pinfunction "P$1_P$1") (pintype "bidirectional"))
      (node (ref "U$5") (pin "L5") (pinfunction "5IN_L5") (pintype "input"))
    )
    (net (code "47") (name "Net-(U$7-1)") (class "Default")
      (node (ref "C19") (pin "1") (pinfunction "1_1") (pintype "passive"))
      (node (ref "R20") (pin "2") (pinfunction "2_2") (pintype "passive"))
      (node (ref "U$7") (pin "P$1") (pinfunction "1_P$1") (pintype "output"))
    )
    (net (code "48") (name "Net-(U$8-~{1})") (class "Default")
      (node (ref "U$2") (pin "OUT1") (pinfunction "OUT1_OUT1") (pintype "bidirectional"))
      (node (ref "U$8") (pin "~1") (pinfunction "~{1}_~1") (pintype "bidirectional"))
    )
    (net (code "49") (name "Net-(U$8-~{2})") (class "Default")
      (node (ref "U$2") (pin "OUT2") (pinfunction "OUT2_OUT2") (pintype "bidirectional"))
      (node (ref "U$8") (pin "~2") (pinfunction "~{2}_~2") (pintype "bidirectional"))
    )
    (net (code "50") (name "Net-(U$12-+VS)") (class "Default")
      (node (ref "C17") (pin "2") (pinfunction "2_2") (pintype "passive"))
      (node (ref "C18") (pin "2") (pinfunction "2_2") (pintype "passive"))
      (node (ref "R17") (pin "2") (pinfunction "2_2") (pintype "passive"))
      (node (ref "U$12") (pin "3") (pinfunction "+VS_3") (pintype "bidirectional"))
    )
    (net (code "51") (name "Net-(U$12-BUFIN)") (class "Default")
      (node (ref "U$12") (pin "10") (pinfunction "IOUT_10") (pintype "bidirectional"))
      (node (ref "U$12") (pin "9") (pinfunction "BUFIN_9") (pintype "bidirectional"))
    )
    (net (code "52") (name "Net-(U$12-CAV)") (class "Default")
      (node (ref "C18") (pin "1") (pinfunction "1_1") (pintype "passive"))
      (node (ref "U$12") (pin "6") (pinfunction "CAV_6") (pintype "bidirectional"))
    )
    (net (code "53") (name "Net-(U$12-COM)") (class "Default")
      (node (ref "C13") (pin "1") (pinfunction "1_1") (pintype "passive"))
      (node (ref "R17") (pin "1") (pinfunction "1_1") (pintype "passive"))
      (node (ref "R18") (pin "2") (pinfunction "2_2") (pintype "passive"))
      (node (ref "U$12") (pin "2") (pinfunction "COM_2") (pintype "bidirectional"))
    )
    (net (code "54") (name "Net-(U$12-VIN)") (class "Default")
      (node (ref "C19") (pin "2") (pinfunction "2_2") (pintype "passive"))
      (node (ref "U$12") (pin "4") (pinfunction "VIN_4") (pintype "bidirectional"))
    )
    (net (code "55") (name "Net-(U$13-+VS)") (class "Default")
      (node (ref "C12") (pin "2") (pinfunction "2_2") (pintype "passive"))
      (node (ref "C14") (pin "2") (pinfunction "2_2") (pintype "passive"))
      (node (ref "R3") (pin "2") (pinfunction "2_2") (pintype "passive"))
      (node (ref "U$13") (pin "3") (pinfunction "+VS_3") (pintype "bidirectional"))
    )
    (net (code "56") (name "Net-(U$13-BUFIN)") (class "Default")
      (node (ref "U$13") (pin "10") (pinfunction "IOUT_10") (pintype "bidirectional"))
      (node (ref "U$13") (pin "9") (pinfunction "BUFIN_9") (pintype "bidirectional"))
    )
    (net (code "57") (name "Net-(U$13-CAV)") (class "Default")
      (node (ref "C12") (pin "1") (pinfunction "1_1") (pintype "passive"))
      (node (ref "U$13") (pin "6") (pinfunction "CAV_6") (pintype "bidirectional"))
    )
    (net (code "58") (name "Net-(U$13-COM)") (class "Default")
      (node (ref "C16") (pin "1") (pinfunction "1_1") (pintype "passive"))
      (node (ref "R3") (pin "1") (pinfunction "1_1") (pintype "passive"))
      (node (ref "R7") (pin "2") (pinfunction "2_2") (pintype "passive"))
      (node (ref "U$13") (pin "2") (pinfunction "COM_2") (pintype "bidirectional"))
    )
    (net (code "59") (name "Net-(U$13-VIN)") (class "Default")
      (node (ref "C11") (pin "2") (pinfunction "2_2") (pintype "passive"))
      (node (ref "U$13") (pin "4") (pinfunction "VIN_4") (pintype "bidirectional"))
    )
    (net (code "60") (name "Net-(U$14-1)") (class "Default")
      (node (ref "C23") (pin "1") (pinfunction "1_1") (pintype "passive"))
      (node (ref "R24") (pin "2") (pinfunction "2_2") (pintype "passive"))
      (node (ref "U$14") (pin "P$1") (pinfunction "1_P$1") (pintype "output"))
    )
    (net (code "61") (name "Net-(U$15-+VS)") (class "Default")
      (node (ref "C21") (pin "1") (pinfunction "1_1") (pintype "passive"))
      (node (ref "C22") (pin "2") (pinfunction "2_2") (pintype "passive"))
      (node (ref "R21") (pin "2") (pinfunction "2_2") (pintype "passive"))
      (node (ref "U$15") (pin "3") (pinfunction "+VS_3") (pintype "bidirectional"))
    )
    (net (code "62") (name "Net-(U$15-BUFIN)") (class "Default")
      (node (ref "U$15") (pin "10") (pinfunction "IOUT_10") (pintype "bidirectional"))
      (node (ref "U$15") (pin "9") (pinfunction "BUFIN_9") (pintype "bidirectional"))
    )
    (net (code "63") (name "Net-(U$15-CAV)") (class "Default")
      (node (ref "C22") (pin "1") (pinfunction "1_1") (pintype "passive"))
      (node (ref "U$15") (pin "6") (pinfunction "CAV_6") (pintype "bidirectional"))
    )
    (net (code "64") (name "Net-(U$15-COM)") (class "Default")
      (node (ref "C20") (pin "1") (pinfunction "1_1") (pintype "passive"))
      (node (ref "R21") (pin "1") (pinfunction "1_1") (pintype "passive"))
      (node (ref "R22") (pin "2") (pinfunction "2_2") (pintype "passive"))
      (node (ref "U$15") (pin "2") (pinfunction "COM_2") (pintype "bidirectional"))
    )
    (net (code "65") (name "Net-(U$15-VIN)") (class "Default")
      (node (ref "C23") (pin "2") (pinfunction "2_2") (pintype "passive"))
      (node (ref "U$15") (pin "4") (pinfunction "VIN_4") (pintype "bidirectional"))
    )
    (net (code "66") (name "Net-(U$17-~{1})") (class "Default")
      (node (ref "U$16") (pin "OUT1") (pinfunction "OUT1_OUT1") (pintype "bidirectional"))
      (node (ref "U$17") (pin "~1") (pinfunction "~{1}_~1") (pintype "bidirectional"))
    )
    (net (code "67") (name "Net-(U$17-~{2})") (class "Default")
      (node (ref "U$16") (pin "OUT2") (pinfunction "OUT2_OUT2") (pintype "bidirectional"))
      (node (ref "U$17") (pin "~2") (pinfunction "~{2}_~2") (pintype "bidirectional"))
    )
    (net (code "68") (name "Net-(U$19-~{1})") (class "Default")
      (node (ref "U$18") (pin "OUT1") (pinfunction "OUT1_OUT1") (pintype "bidirectional"))
      (node (ref "U$19") (pin "~1") (pinfunction "~{1}_~1") (pintype "bidirectional"))
    )
    (net (code "69") (name "Net-(U$19-~{2})") (class "Default")
      (node (ref "U$18") (pin "OUT2") (pinfunction "OUT2_OUT2") (pintype "bidirectional"))
      (node (ref "U$19") (pin "~2") (pinfunction "~{2}_~2") (pintype "bidirectional"))
    )
    (net (code "70") (name "Net-(X2B-S)") (class "Default")
      (node (ref "R39") (pin "1") (pinfunction "1_1") (pintype "passive"))
      (node (ref "X2") (pin "2") (pinfunction "S_2") (pintype "passive"))
    )
    (net (code "71") (name "Net-(X3B-S)") (class "Default")
      (node (ref "R37") (pin "1") (pinfunction "1_1") (pintype "passive"))
      (node (ref "X3") (pin "2") (pinfunction "S_2") (pintype "passive"))
    )
    (net (code "72") (name "Net-(X4B-S)") (class "Default")
      (node (ref "R38") (pin "1") (pinfunction "1_1") (pintype "passive"))
      (node (ref "X4") (pin "2") (pinfunction "S_2") (pintype "passive"))
    )
    (net (code "73") (name "PE") (class "Default")
      (node (ref "U$20") (pin "PE") (pinfunction "PE_PE") (pintype "input"))
      (node (ref "X1") (pin "P$5") (pinfunction "P$5_P$5") (pintype "bidirectional"))
    )
    (net (code "74") (name "unconnected-(AC1002_1-3-PadP$3)") (class "Default")
      (node (ref "AC1002_1") (pin "P$3") (pinfunction "3_P$3") (pintype "no_connect"))
    )
    (net (code "75") (name "unconnected-(U$1-PadNC)") (class "Default")
      (node (ref "U$1") (pin "NC") (pinfunction "NC_NC") (pintype "bidirectional"))
    )
    (net (code "76") (name "unconnected-(U$1-PadNC1)") (class "Default")
      (node (ref "U$1") (pin "NC1") (pinfunction "NC1_NC1") (pintype "bidirectional"))
    )
    (net (code "77") (name "unconnected-(U$3-CLK-PadSCLOCK)") (class "Default")
      (node (ref "U$3") (pin "SCLOCK") (pinfunction "CLK_SCLOCK") (pintype "bidirectional"))
    )
    (net (code "78") (name "unconnected-(U$3-PadGND2)") (class "Default")
      (node (ref "U$3") (pin "GND2") (pinfunction "GND2_GND2") (pintype "bidirectional"))
    )
    (net (code "79") (name "unconnected-(U$3-PadGND3)") (class "Default")
      (node (ref "U$3") (pin "GND3") (pinfunction "GND3_GND3") (pintype "bidirectional"))
    )
    (net (code "80") (name "unconnected-(U$3-PadMISO)") (class "Default")
      (node (ref "U$3") (pin "MISO") (pinfunction "MISO_MISO") (pintype "bidirectional"))
    )
    (net (code "81") (name "unconnected-(U$3-PadMOSI)") (class "Default")
      (node (ref "U$3") (pin "MOSI") (pinfunction "MOSI_MOSI") (pintype "bidirectional"))
    )
    (net (code "82") (name "unconnected-(U$3-VCC2-PadVCC1)") (class "Default")
      (node (ref "U$3") (pin "VCC1") (pinfunction "VCC2_VCC1") (pintype "bidirectional"))
    )
    (net (code "83") (name "unconnected-(U$4-PadP$1)") (class "Default")
      (node (ref "U$4") (pin "P$1") (pinfunction "P$1_P$1") (pintype "bidirectional"))
    )
    (net (code "84") (name "unconnected-(U$4-PadP$6)") (class "Default")
      (node (ref "U$4") (pin "P$6") (pinfunction "P$6_P$6") (pintype "bidirectional"))
    )
    (net (code "85") (name "unconnected-(U$4-PadP$7)") (class "Default")
      (node (ref "U$4") (pin "P$7") (pinfunction "P$7_P$7") (pintype "bidirectional"))
    )
    (net (code "86") (name "unconnected-(U$4-PadP$8)") (class "Default")
      (node (ref "U$4") (pin "P$8") (pinfunction "P$8_P$8") (pintype "bidirectional"))
    )
    (net (code "87") (name "unconnected-(U$4-PadP$10)") (class "Default")
      (node (ref "U$4") (pin "P$10") (pinfunction "P$10_P$10") (pintype "bidirectional"))
    )
    (net (code "88") (name "unconnected-(U$4-PadP$11)") (class "Default")
      (node (ref "U$4") (pin "P$11") (pinfunction "P$11_P$11") (pintype "bidirectional"))
    )
    (net (code "89") (name "unconnected-(U$4-PadP$12)") (class "Default")
      (node (ref "U$4") (pin "P$12") (pinfunction "P$12_P$12") (pintype "bidirectional"))
    )
    (net (code "90") (name "unconnected-(U$4-PadP$13)") (class "Default")
      (node (ref "U$4") (pin "P$13") (pinfunction "P$13_P$13") (pintype "bidirectional"))
    )
    (net (code "91") (name "unconnected-(U$4-PadP$14)") (class "Default")
      (node (ref "U$4") (pin "P$14") (pinfunction "P$14_P$14") (pintype "bidirectional"))
    )
    (net (code "92") (name "unconnected-(U$4-PadP$15)") (class "Default")
      (node (ref "U$4") (pin "P$15") (pinfunction "P$15_P$15") (pintype "bidirectional"))
    )
    (net (code "93") (name "unconnected-(U$4-PadP$18)") (class "Default")
      (node (ref "U$4") (pin "P$18") (pinfunction "P$18_P$18") (pintype "bidirectional"))
    )
    (net (code "94") (name "unconnected-(U$4-PadP$19)") (class "Default")
      (node (ref "U$4") (pin "P$19") (pinfunction "P$19_P$19") (pintype "bidirectional"))
    )
    (net (code "95") (name "unconnected-(U$4-PadP$22)") (class "Default")
      (node (ref "U$4") (pin "P$22") (pinfunction "P$22_P$22") (pintype "bidirectional"))
    )
    (net (code "96") (name "unconnected-(U$4-PadP$23)") (class "Default")
      (node (ref "U$4") (pin "P$23") (pinfunction "P$23_P$23") (pintype "bidirectional"))
    )
    (net (code "97") (name "unconnected-(U$4-PadP$24)") (class "Default")
      (node (ref "U$4") (pin "P$24") (pinfunction "P$24_P$24") (pintype "bidirectional"))
    )
    (net (code "98") (name "unconnected-(U$4-PadP$26)") (class "Default")
      (node (ref "U$4") (pin "P$26") (pinfunction "P$26_P$26") (pintype "bidirectional"))
    )
    (net (code "99") (name "unconnected-(U$4-PadP$27)") (class "Default")
      (node (ref "U$4") (pin "P$27") (pinfunction "P$27_P$27") (pintype "bidirectional"))
    )
    (net (code "100") (name "unconnected-(U$4-PadP$28)") (class "Default")
      (node (ref "U$4") (pin "P$28") (pinfunction "P$28_P$28") (pintype "bidirectional"))
    )
    (net (code "101") (name "unconnected-(U$4-PadP$29)") (class "Default")
      (node (ref "U$4") (pin "P$29") (pinfunction "P$29_P$29") (pintype "bidirectional"))
    )
    (net (code "102") (name "unconnected-(U$4-PadP$30)") (class "Default")
      (node (ref "U$4") (pin "P$30") (pinfunction "P$30_P$30") (pintype "bidirectional"))
    )
    (net (code "103") (name "unconnected-(U$4-PadP$31)") (class "Default")
      (node (ref "U$4") (pin "P$31") (pinfunction "P$31_P$31") (pintype "bidirectional"))
    )
    (net (code "104") (name "unconnected-(U$7-3-PadP$3)") (class "Default")
      (node (ref "U$7") (pin "P$3") (pinfunction "3_P$3") (pintype "no_connect"))
    )
    (net (code "105") (name "unconnected-(U$12-DB-Pad7)") (class "Default")
      (node (ref "U$12") (pin "7") (pinfunction "DB_7") (pintype "bidirectional"))
    )
    (net (code "106") (name "unconnected-(U$12-RL-Pad1)") (class "Default")
      (node (ref "U$12") (pin "1") (pinfunction "RL_1") (pintype "bidirectional"))
    )
    (net (code "107") (name "unconnected-(U$13-DB-Pad7)") (class "Default")
      (node (ref "U$13") (pin "7") (pinfunction "DB_7") (pintype "bidirectional"))
    )
    (net (code "108") (name "unconnected-(U$13-RL-Pad1)") (class "Default")
      (node (ref "U$13") (pin "1") (pinfunction "RL_1") (pintype "bidirectional"))
    )
    (net (code "109") (name "unconnected-(U$14-3-PadP$3)") (class "Default")
      (node (ref "U$14") (pin "P$3") (pinfunction "3_P$3") (pintype "no_connect"))
    )
    (net (code "110") (name "unconnected-(U$15-DB-Pad7)") (class "Default")
      (node (ref "U$15") (pin "7") (pinfunction "DB_7") (pintype "bidirectional"))
    )
    (net (code "111") (name "unconnected-(U$15-RL-Pad1)") (class "Default")
      (node (ref "U$15") (pin "1") (pinfunction "RL_1") (pintype "bidirectional"))
    )
  )
)
